# debug.net
KiCad netlist of a schematic drawn in Altium Designer
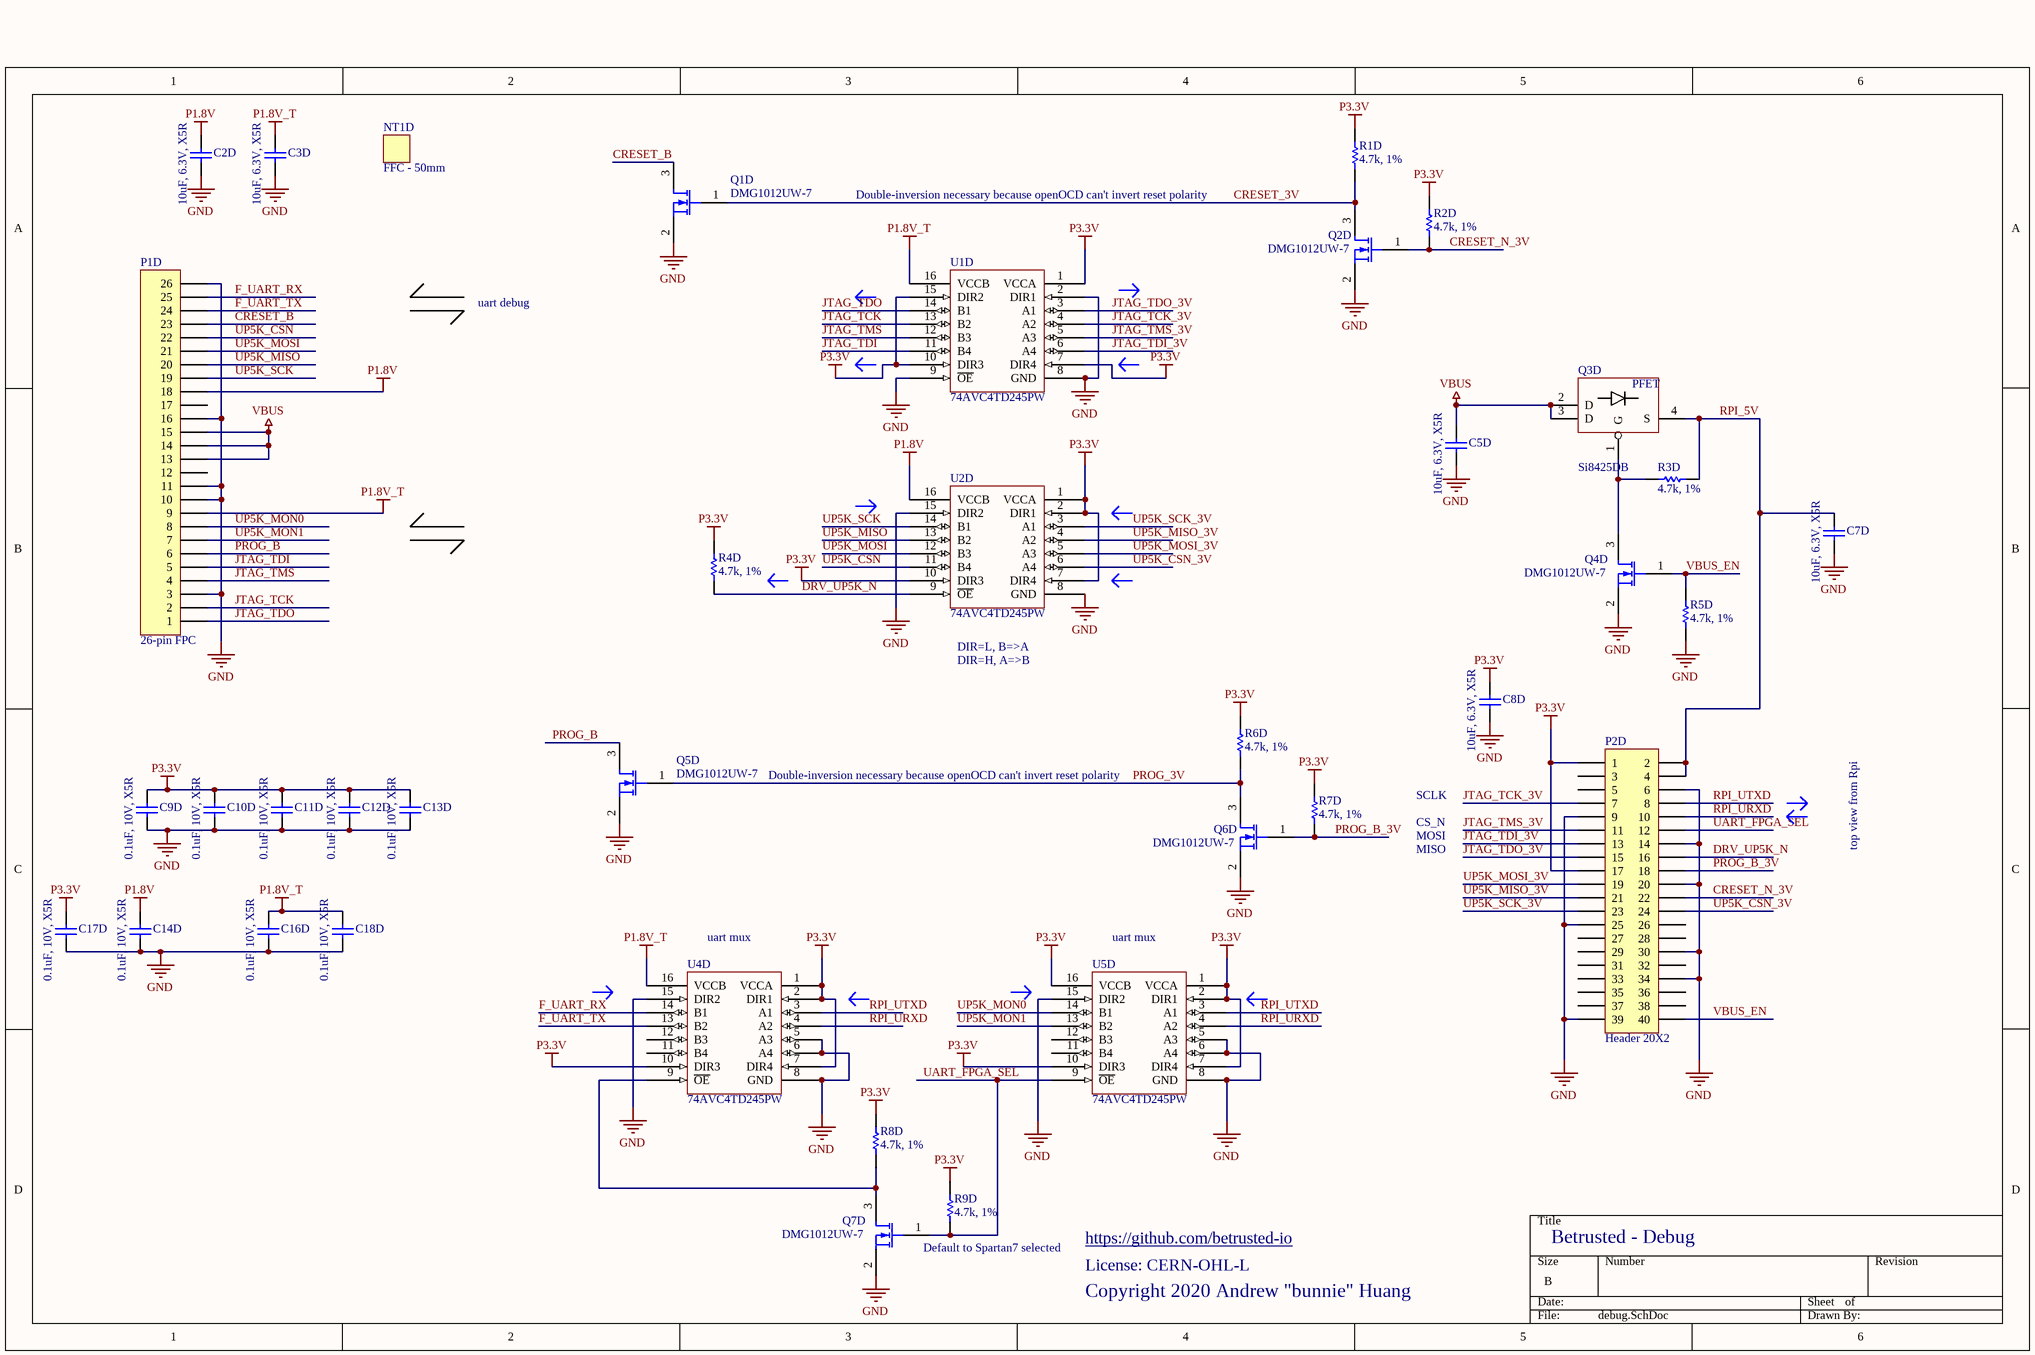
[diagram p0: debug.SchDoc]

(export (version "E")
  (design (tool "Eeschema 10.0.6"))
  (components
    (comp (ref "C2D")
      (value "10uF, 6.3V, X5R")
      (footprint "B_CAP0603")
      (description "Capacitor (Semiconductor SIM Model)")
      (fields (field (name "MPN") "CL10A106MQ8NNNC"))
      (libsource (lib "Miscellaneous Devices") (part "Cap Semi"))
    )
    (comp (ref "C3D")
      (value "10uF, 6.3V, X5R")
      (footprint "B_CAP0603")
      (description "Capacitor (Semiconductor SIM Model)")
      (fields (field (name "MPN") "CL10A106MQ8NNNC"))
      (libsource (lib "Miscellaneous Devices") (part "Cap Semi"))
    )
    (comp (ref "C5D")
      (value "10uF, 6.3V, X5R")
      (footprint "B_CAP0603")
      (description "Capacitor (Semiconductor SIM Model)")
      (fields (field (name "MPN") "CL10A106MQ8NNNC"))
      (libsource (lib "Miscellaneous Devices") (part "Cap Semi"))
    )
    (comp (ref "C7D")
      (value "10uF, 6.3V, X5R")
      (footprint "B_CAP0603")
      (description "Capacitor (Semiconductor SIM Model)")
      (fields (field (name "MPN") "CL10A106MQ8NNNC"))
      (libsource (lib "Miscellaneous Devices") (part "Cap Semi"))
    )
    (comp (ref "C8D")
      (value "10uF, 6.3V, X5R")
      (footprint "B_CAP0603")
      (description "Capacitor (Semiconductor SIM Model)")
      (fields (field (name "MPN") "CL10A106MQ8NNNC"))
      (libsource (lib "Miscellaneous Devices") (part "Cap Semi"))
    )
    (comp (ref "C9D")
      (value "0.1uF, 10V, X5R")
      (footprint "B_CAP0402")
      (description "Capacitor (Semiconductor SIM Model)")
      (fields (field (name "MPN") "CL05A104KP5NNNC"))
      (libsource (lib "Miscellaneous Devices") (part "Cap Semi"))
    )
    (comp (ref "C10D")
      (value "0.1uF, 10V, X5R")
      (footprint "B_CAP0402")
      (description "Capacitor (Semiconductor SIM Model)")
      (fields (field (name "MPN") "CL05A104KP5NNNC"))
      (libsource (lib "Miscellaneous Devices") (part "Cap Semi"))
    )
    (comp (ref "C11D")
      (value "0.1uF, 10V, X5R")
      (footprint "B_CAP0402")
      (description "Capacitor (Semiconductor SIM Model)")
      (fields (field (name "MPN") "CL05A104KP5NNNC"))
      (libsource (lib "Miscellaneous Devices") (part "Cap Semi"))
    )
    (comp (ref "C12D")
      (value "0.1uF, 10V, X5R")
      (footprint "B_CAP0402")
      (description "Capacitor (Semiconductor SIM Model)")
      (fields (field (name "MPN") "CL05A104KP5NNNC"))
      (libsource (lib "Miscellaneous Devices") (part "Cap Semi"))
    )
    (comp (ref "C13D")
      (value "0.1uF, 10V, X5R")
      (footprint "B_CAP0402")
      (description "Capacitor (Semiconductor SIM Model)")
      (fields (field (name "MPN") "CL05A104KP5NNNC"))
      (libsource (lib "Miscellaneous Devices") (part "Cap Semi"))
    )
    (comp (ref "C14D")
      (value "0.1uF, 10V, X5R")
      (footprint "B_CAP0402")
      (description "Capacitor (Semiconductor SIM Model)")
      (fields (field (name "MPN") "CL05A104KP5NNNC"))
      (libsource (lib "Miscellaneous Devices") (part "Cap Semi"))
    )
    (comp (ref "C16D")
      (value "0.1uF, 10V, X5R")
      (footprint "B_CAP0402")
      (description "Capacitor (Semiconductor SIM Model)")
      (fields (field (name "MPN") "CL05A104KP5NNNC"))
      (libsource (lib "Miscellaneous Devices") (part "Cap Semi"))
    )
    (comp (ref "C17D")
      (value "0.1uF, 10V, X5R")
      (footprint "B_CAP0402")
      (description "Capacitor (Semiconductor SIM Model)")
      (fields (field (name "MPN") "CL05A104KP5NNNC"))
      (libsource (lib "Miscellaneous Devices") (part "Cap Semi"))
    )
    (comp (ref "C18D")
      (value "0.1uF, 10V, X5R")
      (footprint "B_CAP0402")
      (description "Capacitor (Semiconductor SIM Model)")
      (fields (field (name "MPN") "CL05A104KP5NNNC"))
      (libsource (lib "Miscellaneous Devices") (part "Cap Semi"))
    )
    (comp (ref "NT1D")
      (value "FFC - 50mm")
      (description "Placeholder for non-board BOM items")
      (fields (field (name "MPN") "FJH-26-D-02.00-4"))
      (libsource (lib "commonsch") (part "NOTE"))
    )
    (comp (ref "P1D")
      (value "26-pin FPC")
      (footprint "HRS_FH34SRJ-26S-0.5SH(50)")
      (description "26 Pin FPC header")
      (fields (field (name "MPN") "FH34SRJ-26S-0.5SH(99)"))
      (libsource (lib "commonsch-new") (part "FPC-26"))
    )
    (comp (ref "P2D")
      (value "Header 20X2")
      (footprint "SAMTEC_SSW-120-01-F-D")
      (description "Header, 20-Pin, Dual row")
      (fields (field (name "MPN") "CS25402-40G-S85-C") (field (name "PUBLISHER") "Altium Limited"))
      (libsource (lib "Miscellaneous Connectors") (part "Header 20X2"))
    )
    (comp (ref "Q1D")
      (value "DMG1012UW-7")
      (footprint "SOT323-3AN")
      (description "N-Channel MOSFET")
      (fields (field (name "PUBLISHER") "Altium Limited"))
      (libsource (lib "Miscellaneous Devices") (part "MOSFET-N"))
    )
    (comp (ref "Q2D")
      (value "DMG1012UW-7")
      (footprint "SOT323-3AN")
      (description "N-Channel MOSFET")
      (fields (field (name "PUBLISHER") "Altium Limited"))
      (libsource (lib "Miscellaneous Devices") (part "MOSFET-N"))
    )
    (comp (ref "Q3D")
      (value "Si8425DB")
      (footprint "VISHAY_MICRO_FOOT_4_BUMP")
      (description "P-channel 20V 6.2A 27mOhm @ -2.5V")
      (fields (field (name "MPN") "SI8425DB-T1-E1"))
      (libsource (lib "temp-to-merge") (part "Si8425DB"))
    )
    (comp (ref "Q4D")
      (value "DMG1012UW-7")
      (footprint "SOT323-3AN")
      (description "N-Channel MOSFET")
      (fields (field (name "PUBLISHER") "Altium Limited"))
      (libsource (lib "Miscellaneous Devices") (part "MOSFET-N"))
    )
    (comp (ref "Q5D")
      (value "DMG1012UW-7")
      (footprint "SOT323-3AN")
      (description "N-Channel MOSFET")
      (fields (field (name "PUBLISHER") "Altium Limited"))
      (libsource (lib "Miscellaneous Devices") (part "MOSFET-N"))
    )
    (comp (ref "Q6D")
      (value "DMG1012UW-7")
      (footprint "SOT323-3AN")
      (description "N-Channel MOSFET")
      (fields (field (name "PUBLISHER") "Altium Limited"))
      (libsource (lib "Miscellaneous Devices") (part "MOSFET-N"))
    )
    (comp (ref "Q7D")
      (value "DMG1012UW-7")
      (footprint "SOT323-3AN")
      (description "N-Channel MOSFET")
      (fields (field (name "PUBLISHER") "Altium Limited"))
      (libsource (lib "Miscellaneous Devices") (part "MOSFET-N"))
    )
    (comp (ref "R1D")
      (value "4.7k, 1%")
      (footprint "B_RES0402")
      (description "Resistor")
      (fields (field (name "MPN") "ANY"))
      (libsource (lib "Miscellaneous Devices") (part "Res1"))
    )
    (comp (ref "R2D")
      (value "4.7k, 1%")
      (footprint "B_RES0402")
      (description "Resistor")
      (fields (field (name "MPN") "ANY"))
      (libsource (lib "Miscellaneous Devices") (part "Res1"))
    )
    (comp (ref "R3D")
      (value "4.7k, 1%")
      (footprint "B_RES0402")
      (description "Resistor")
      (fields (field (name "MPN") "ANY"))
      (libsource (lib "Miscellaneous Devices") (part "Res1"))
    )
    (comp (ref "R4D")
      (value "4.7k, 1%")
      (footprint "B_RES0402")
      (description "Resistor")
      (fields (field (name "MPN") "ANY"))
      (libsource (lib "Miscellaneous Devices") (part "Res1"))
    )
    (comp (ref "R5D")
      (value "4.7k, 1%")
      (footprint "B_RES0402")
      (description "Resistor")
      (fields (field (name "MPN") "ANY"))
      (libsource (lib "Miscellaneous Devices") (part "Res1"))
    )
    (comp (ref "R6D")
      (value "4.7k, 1%")
      (footprint "B_RES0402")
      (description "Resistor")
      (fields (field (name "MPN") "ANY"))
      (libsource (lib "Miscellaneous Devices") (part "Res1"))
    )
    (comp (ref "R7D")
      (value "4.7k, 1%")
      (footprint "B_RES0402")
      (description "Resistor")
      (fields (field (name "MPN") "ANY"))
      (libsource (lib "Miscellaneous Devices") (part "Res1"))
    )
    (comp (ref "R8D")
      (value "4.7k, 1%")
      (footprint "B_RES0402")
      (description "Resistor")
      (fields (field (name "MPN") "ANY"))
      (libsource (lib "Miscellaneous Devices") (part "Res1"))
    )
    (comp (ref "R9D")
      (value "4.7k, 1%")
      (footprint "B_RES0402")
      (description "Resistor")
      (fields (field (name "MPN") "ANY"))
      (libsource (lib "Miscellaneous Devices") (part "Res1"))
    )
    (comp (ref "U1D")
      (value "74AVC4TD245PW")
      (footprint "TSOP65P640-16AN")
      (description "4-bit dual supply translating transceiver with configurable voltage translation; 3-state")
      (libsource (lib "commonsch-new") (part "74AVC4TD245"))
    )
    (comp (ref "U2D")
      (value "74AVC4TD245PW")
      (footprint "TSOP65P640-16AN")
      (description "4-bit dual supply translating transceiver with configurable voltage translation; 3-state")
      (libsource (lib "commonsch-new") (part "74AVC4TD245"))
    )
    (comp (ref "U4D")
      (value "74AVC4TD245PW")
      (footprint "TSOP65P640-16AN")
      (description "4-bit dual supply translating transceiver with configurable voltage translation; 3-state")
      (libsource (lib "commonsch-new") (part "74AVC4TD245"))
    )
    (comp (ref "U5D")
      (value "74AVC4TD245PW")
      (footprint "TSOP65P640-16AN")
      (description "4-bit dual supply translating transceiver with configurable voltage translation; 3-state")
      (libsource (lib "commonsch-new") (part "74AVC4TD245"))
    )
  )
  (nets
    (net (code "1") (name "/CRESET_3V") (class "Default")
      (node (ref "Q1D") (pin "1") (pinfunction "G_1") (pintype "passive"))
      (node (ref "Q2D") (pin "3") (pinfunction "D_3") (pintype "passive"))
      (node (ref "R1D") (pin "1") (pinfunction "1_1") (pintype "passive"))
    )
    (net (code "2") (name "/CRESET_B") (class "Default")
      (node (ref "P1D") (pin "23") (pinfunction "23_23") (pintype "passive"))
      (node (ref "Q1D") (pin "3") (pinfunction "D_3") (pintype "passive"))
    )
    (net (code "3") (name "/CRESET_N_3V") (class "Default")
      (node (ref "P2D") (pin "22") (pinfunction "22_22") (pintype "passive"))
      (node (ref "Q2D") (pin "1") (pinfunction "G_1") (pintype "passive"))
      (node (ref "R2D") (pin "1") (pinfunction "1_1") (pintype "passive"))
    )
    (net (code "4") (name "/DRV_UP5K_N") (class "Default")
      (node (ref "P2D") (pin "16") (pinfunction "16_16") (pintype "passive"))
      (node (ref "R4D") (pin "1") (pinfunction "1_1") (pintype "passive"))
      (node (ref "U2D") (pin "9") (pinfunction "~{OE}_9") (pintype "input"))
    )
    (net (code "5") (name "/F_UART_RX") (class "Default")
      (node (ref "P1D") (pin "25") (pinfunction "25_25") (pintype "passive"))
      (node (ref "U4D") (pin "14") (pinfunction "B1_14") (pintype "bidirectional"))
    )
    (net (code "6") (name "/F_UART_TX") (class "Default")
      (node (ref "P1D") (pin "24") (pinfunction "24_24") (pintype "passive"))
      (node (ref "U4D") (pin "13") (pinfunction "B2_13") (pintype "bidirectional"))
    )
    (net (code "7") (name "/JTAG_TCK") (class "Default")
      (node (ref "P1D") (pin "2") (pinfunction "2_2") (pintype "passive"))
      (node (ref "U1D") (pin "13") (pinfunction "B2_13") (pintype "bidirectional"))
    )
    (net (code "8") (name "/JTAG_TCK_3V") (class "Default")
      (node (ref "P2D") (pin "7") (pinfunction "7_7") (pintype "passive"))
      (node (ref "U1D") (pin "4") (pinfunction "A2_4") (pintype "bidirectional"))
    )
    (net (code "9") (name "/JTAG_TDI") (class "Default")
      (node (ref "P1D") (pin "5") (pinfunction "5_5") (pintype "passive"))
      (node (ref "U1D") (pin "11") (pinfunction "B4_11") (pintype "bidirectional"))
    )
    (net (code "10") (name "/JTAG_TDI_3V") (class "Default")
      (node (ref "P2D") (pin "13") (pinfunction "13_13") (pintype "passive"))
      (node (ref "U1D") (pin "6") (pinfunction "A4_6") (pintype "bidirectional"))
    )
    (net (code "11") (name "/JTAG_TDO") (class "Default")
      (node (ref "P1D") (pin "1") (pinfunction "1_1") (pintype "passive"))
      (node (ref "U1D") (pin "14") (pinfunction "B1_14") (pintype "bidirectional"))
    )
    (net (code "12") (name "/JTAG_TDO_3V") (class "Default")
      (node (ref "P2D") (pin "15") (pinfunction "15_15") (pintype "passive"))
      (node (ref "U1D") (pin "3") (pinfunction "A1_3") (pintype "bidirectional"))
    )
    (net (code "13") (name "/JTAG_TMS") (class "Default")
      (node (ref "P1D") (pin "4") (pinfunction "4_4") (pintype "passive"))
      (node (ref "U1D") (pin "12") (pinfunction "B3_12") (pintype "bidirectional"))
    )
    (net (code "14") (name "/JTAG_TMS_3V") (class "Default")
      (node (ref "P2D") (pin "11") (pinfunction "11_11") (pintype "passive"))
      (node (ref "U1D") (pin "5") (pinfunction "A3_5") (pintype "bidirectional"))
    )
    (net (code "15") (name "/PROG_3V") (class "Default")
      (node (ref "Q5D") (pin "1") (pinfunction "G_1") (pintype "passive"))
      (node (ref "Q6D") (pin "3") (pinfunction "D_3") (pintype "passive"))
      (node (ref "R6D") (pin "1") (pinfunction "1_1") (pintype "passive"))
    )
    (net (code "16") (name "/PROG_B") (class "Default")
      (node (ref "P1D") (pin "6") (pinfunction "6_6") (pintype "passive"))
      (node (ref "Q5D") (pin "3") (pinfunction "D_3") (pintype "passive"))
    )
    (net (code "17") (name "/PROG_B_3V") (class "Default")
      (node (ref "P2D") (pin "18") (pinfunction "18_18") (pintype "passive"))
      (node (ref "Q6D") (pin "1") (pinfunction "G_1") (pintype "passive"))
      (node (ref "R7D") (pin "1") (pinfunction "1_1") (pintype "passive"))
    )
    (net (code "18") (name "/RPI_5V") (class "Default")
      (node (ref "C7D") (pin "1") (pinfunction "1_1") (pintype "passive"))
      (node (ref "P2D") (pin "2") (pinfunction "2_2") (pintype "passive"))
      (node (ref "P2D") (pin "4") (pinfunction "4_4") (pintype "passive"))
      (node (ref "Q3D") (pin "4") (pinfunction "S_4") (pintype "passive"))
      (node (ref "R3D") (pin "1") (pinfunction "1_1") (pintype "passive"))
    )
    (net (code "19") (name "/RPI_URXD") (class "Default")
      (node (ref "P2D") (pin "10") (pinfunction "10_10") (pintype "passive"))
      (node (ref "U4D") (pin "4") (pinfunction "A2_4") (pintype "bidirectional"))
      (node (ref "U5D") (pin "4") (pinfunction "A2_4") (pintype "bidirectional"))
    )
    (net (code "20") (name "/RPI_UTXD") (class "Default")
      (node (ref "P2D") (pin "8") (pinfunction "8_8") (pintype "passive"))
      (node (ref "U4D") (pin "3") (pinfunction "A1_3") (pintype "bidirectional"))
      (node (ref "U5D") (pin "3") (pinfunction "A1_3") (pintype "bidirectional"))
    )
    (net (code "21") (name "/UART_FPGA_SEL") (class "Default")
      (node (ref "P2D") (pin "12") (pinfunction "12_12") (pintype "passive"))
      (node (ref "Q7D") (pin "1") (pinfunction "G_1") (pintype "passive"))
      (node (ref "R9D") (pin "1") (pinfunction "1_1") (pintype "passive"))
      (node (ref "U5D") (pin "9") (pinfunction "~{OE}_9") (pintype "input"))
    )
    (net (code "22") (name "/UP5K_CSN") (class "Default")
      (node (ref "P1D") (pin "22") (pinfunction "22_22") (pintype "passive"))
      (node (ref "U2D") (pin "11") (pinfunction "B4_11") (pintype "bidirectional"))
    )
    (net (code "23") (name "/UP5K_CSN_3V") (class "Default")
      (node (ref "P2D") (pin "24") (pinfunction "24_24") (pintype "passive"))
      (node (ref "U2D") (pin "6") (pinfunction "A4_6") (pintype "bidirectional"))
    )
    (net (code "24") (name "/UP5K_MISO") (class "Default")
      (node (ref "P1D") (pin "20") (pinfunction "20_20") (pintype "passive"))
      (node (ref "U2D") (pin "13") (pinfunction "B2_13") (pintype "bidirectional"))
    )
    (net (code "25") (name "/UP5K_MISO_3V") (class "Default")
      (node (ref "P2D") (pin "21") (pinfunction "21_21") (pintype "passive"))
      (node (ref "U2D") (pin "4") (pinfunction "A2_4") (pintype "bidirectional"))
    )
    (net (code "26") (name "/UP5K_MON0") (class "Default")
      (node (ref "P1D") (pin "8") (pinfunction "8_8") (pintype "passive"))
      (node (ref "U5D") (pin "14") (pinfunction "B1_14") (pintype "bidirectional"))
    )
    (net (code "27") (name "/UP5K_MON1") (class "Default")
      (node (ref "P1D") (pin "7") (pinfunction "7_7") (pintype "passive"))
      (node (ref "U5D") (pin "13") (pinfunction "B2_13") (pintype "bidirectional"))
    )
    (net (code "28") (name "/UP5K_MOSI") (class "Default")
      (node (ref "P1D") (pin "21") (pinfunction "21_21") (pintype "passive"))
      (node (ref "U2D") (pin "12") (pinfunction "B3_12") (pintype "bidirectional"))
    )
    (net (code "29") (name "/UP5K_MOSI_3V") (class "Default")
      (node (ref "P2D") (pin "19") (pinfunction "19_19") (pintype "passive"))
      (node (ref "U2D") (pin "5") (pinfunction "A3_5") (pintype "bidirectional"))
    )
    (net (code "30") (name "/UP5K_SCK") (class "Default")
      (node (ref "P1D") (pin "19") (pinfunction "19_19") (pintype "passive"))
      (node (ref "U2D") (pin "14") (pinfunction "B1_14") (pintype "bidirectional"))
    )
    (net (code "31") (name "/UP5K_SCK_3V") (class "Default")
      (node (ref "P2D") (pin "23") (pinfunction "23_23") (pintype "passive"))
      (node (ref "U2D") (pin "3") (pinfunction "A1_3") (pintype "bidirectional"))
    )
    (net (code "32") (name "/VBUS_EN") (class "Default")
      (node (ref "P2D") (pin "40") (pinfunction "40_40") (pintype "passive"))
      (node (ref "Q4D") (pin "1") (pinfunction "G_1") (pintype "passive"))
      (node (ref "R5D") (pin "2") (pinfunction "2_2") (pintype "passive"))
    )
    (net (code "33") (name "GND") (class "Default")
      (node (ref "C10D") (pin "2") (pinfunction "2_2") (pintype "passive"))
      (node (ref "C11D") (pin "2") (pinfunction "2_2") (pintype "passive"))
      (node (ref "C12D") (pin "2") (pinfunction "2_2") (pintype "passive"))
      (node (ref "C13D") (pin "2") (pinfunction "2_2") (pintype "passive"))
      (node (ref "C14D") (pin "2") (pinfunction "2_2") (pintype "passive"))
      (node (ref "C16D") (pin "2") (pinfunction "2_2") (pintype "passive"))
      (node (ref "C17D") (pin "2") (pinfunction "2_2") (pintype "passive"))
      (node (ref "C18D") (pin "2") (pinfunction "2_2") (pintype "passive"))
      (node (ref "C2D") (pin "2") (pinfunction "2_2") (pintype "passive"))
      (node (ref "C3D") (pin "2") (pinfunction "2_2") (pintype "passive"))
      (node (ref "C5D") (pin "2") (pinfunction "2_2") (pintype "passive"))
      (node (ref "C7D") (pin "2") (pinfunction "2_2") (pintype "passive"))
      (node (ref "C8D") (pin "2") (pinfunction "2_2") (pintype "passive"))
      (node (ref "C9D") (pin "2") (pinfunction "2_2") (pintype "passive"))
      (node (ref "P1D") (pin "10") (pinfunction "10_10") (pintype "passive"))
      (node (ref "P1D") (pin "11") (pinfunction "11_11") (pintype "passive"))
      (node (ref "P1D") (pin "16") (pinfunction "16_16") (pintype "passive"))
      (node (ref "P1D") (pin "26") (pinfunction "26_26") (pintype "passive"))
      (node (ref "P1D") (pin "3") (pinfunction "3_3") (pintype "passive"))
      (node (ref "P2D") (pin "14") (pinfunction "14_14") (pintype "passive"))
      (node (ref "P2D") (pin "20") (pinfunction "20_20") (pintype "passive"))
      (node (ref "P2D") (pin "25") (pinfunction "25_25") (pintype "passive"))
      (node (ref "P2D") (pin "30") (pinfunction "30_30") (pintype "passive"))
      (node (ref "P2D") (pin "34") (pinfunction "34_34") (pintype "passive"))
      (node (ref "P2D") (pin "39") (pinfunction "39_39") (pintype "passive"))
      (node (ref "P2D") (pin "6") (pinfunction "6_6") (pintype "passive"))
      (node (ref "P2D") (pin "9") (pinfunction "9_9") (pintype "passive"))
      (node (ref "Q1D") (pin "2") (pinfunction "S_2") (pintype "passive"))
      (node (ref "Q2D") (pin "2") (pinfunction "S_2") (pintype "passive"))
      (node (ref "Q4D") (pin "2") (pinfunction "S_2") (pintype "passive"))
      (node (ref "Q5D") (pin "2") (pinfunction "S_2") (pintype "passive"))
      (node (ref "Q6D") (pin "2") (pinfunction "S_2") (pintype "passive"))
      (node (ref "Q7D") (pin "2") (pinfunction "S_2") (pintype "passive"))
      (node (ref "R5D") (pin "1") (pinfunction "1_1") (pintype "passive"))
      (node (ref "U1D") (pin "2") (pinfunction "DIR1_2") (pintype "input"))
      (node (ref "U1D") (pin "8") (pinfunction "GND_8") (pintype "power_in"))
      (node (ref "U1D") (pin "9") (pinfunction "~{OE}_9") (pintype "input"))
      (node (ref "U2D") (pin "15") (pinfunction "DIR2_15") (pintype "input"))
      (node (ref "U2D") (pin "8") (pinfunction "GND_8") (pintype "power_in"))
      (node (ref "U4D") (pin "15") (pinfunction "DIR2_15") (pintype "input"))
      (node (ref "U4D") (pin "5") (pinfunction "A3_5") (pintype "bidirectional"))
      (node (ref "U4D") (pin "6") (pinfunction "A4_6") (pintype "bidirectional"))
      (node (ref "U4D") (pin "8") (pinfunction "GND_8") (pintype "power_in"))
      (node (ref "U5D") (pin "15") (pinfunction "DIR2_15") (pintype "input"))
      (node (ref "U5D") (pin "5") (pinfunction "A3_5") (pintype "bidirectional"))
      (node (ref "U5D") (pin "6") (pinfunction "A4_6") (pintype "bidirectional"))
      (node (ref "U5D") (pin "8") (pinfunction "GND_8") (pintype "power_in"))
    )
    (net (code "34") (name "Net-(Q3D-G)") (class "Default")
      (node (ref "Q3D") (pin "1") (pinfunction "G_1") (pintype "passive"))
      (node (ref "Q4D") (pin "3") (pinfunction "D_3") (pintype "passive"))
      (node (ref "R3D") (pin "2") (pinfunction "2_2") (pintype "passive"))
    )
    (net (code "35") (name "Net-(Q7D-D)") (class "Default")
      (node (ref "Q7D") (pin "3") (pinfunction "D_3") (pintype "passive"))
      (node (ref "R8D") (pin "1") (pinfunction "1_1") (pintype "passive"))
      (node (ref "U4D") (pin "9") (pinfunction "~{OE}_9") (pintype "input"))
    )
    (net (code "36") (name "P1.8V") (class "Default")
      (node (ref "C14D") (pin "1") (pinfunction "1_1") (pintype "passive"))
      (node (ref "C2D") (pin "1") (pinfunction "1_1") (pintype "passive"))
      (node (ref "P1D") (pin "18") (pinfunction "18_18") (pintype "passive"))
      (node (ref "U2D") (pin "16") (pinfunction "VCCB_16") (pintype "power_in"))
    )
    (net (code "37") (name "P1.8V_T") (class "Default")
      (node (ref "C16D") (pin "1") (pinfunction "1_1") (pintype "passive"))
      (node (ref "C18D") (pin "1") (pinfunction "1_1") (pintype "passive"))
      (node (ref "C3D") (pin "1") (pinfunction "1_1") (pintype "passive"))
      (node (ref "P1D") (pin "9") (pinfunction "9_9") (pintype "passive"))
      (node (ref "U1D") (pin "16") (pinfunction "VCCB_16") (pintype "power_in"))
      (node (ref "U4D") (pin "16") (pinfunction "VCCB_16") (pintype "power_in"))
    )
    (net (code "38") (name "P3.3V") (class "Default")
      (node (ref "C10D") (pin "1") (pinfunction "1_1") (pintype "passive"))
      (node (ref "C11D") (pin "1") (pinfunction "1_1") (pintype "passive"))
      (node (ref "C12D") (pin "1") (pinfunction "1_1") (pintype "passive"))
      (node (ref "C13D") (pin "1") (pinfunction "1_1") (pintype "passive"))
      (node (ref "C17D") (pin "1") (pinfunction "1_1") (pintype "passive"))
      (node (ref "C8D") (pin "1") (pinfunction "1_1") (pintype "passive"))
      (node (ref "C9D") (pin "1") (pinfunction "1_1") (pintype "passive"))
      (node (ref "P2D") (pin "1") (pinfunction "1_1") (pintype "passive"))
      (node (ref "P2D") (pin "17") (pinfunction "17_17") (pintype "passive"))
      (node (ref "R1D") (pin "2") (pinfunction "2_2") (pintype "passive"))
      (node (ref "R2D") (pin "2") (pinfunction "2_2") (pintype "passive"))
      (node (ref "R4D") (pin "2") (pinfunction "2_2") (pintype "passive"))
      (node (ref "R6D") (pin "2") (pinfunction "2_2") (pintype "passive"))
      (node (ref "R7D") (pin "2") (pinfunction "2_2") (pintype "passive"))
      (node (ref "R8D") (pin "2") (pinfunction "2_2") (pintype "passive"))
      (node (ref "R9D") (pin "2") (pinfunction "2_2") (pintype "passive"))
      (node (ref "U1D") (pin "1") (pinfunction "VCCA_1") (pintype "power_in"))
      (node (ref "U1D") (pin "10") (pinfunction "DIR3_10") (pintype "input"))
      (node (ref "U1D") (pin "15") (pinfunction "DIR2_15") (pintype "input"))
      (node (ref "U1D") (pin "7") (pinfunction "DIR4_7") (pintype "input"))
      (node (ref "U2D") (pin "1") (pinfunction "VCCA_1") (pintype "power_in"))
      (node (ref "U2D") (pin "10") (pinfunction "DIR3_10") (pintype "input"))
      (node (ref "U2D") (pin "2") (pinfunction "DIR1_2") (pintype "input"))
      (node (ref "U2D") (pin "7") (pinfunction "DIR4_7") (pintype "input"))
      (node (ref "U4D") (pin "1") (pinfunction "VCCA_1") (pintype "power_in"))
      (node (ref "U4D") (pin "10") (pinfunction "DIR3_10") (pintype "input"))
      (node (ref "U4D") (pin "2") (pinfunction "DIR1_2") (pintype "input"))
      (node (ref "U4D") (pin "7") (pinfunction "DIR4_7") (pintype "input"))
      (node (ref "U5D") (pin "1") (pinfunction "VCCA_1") (pintype "power_in"))
      (node (ref "U5D") (pin "10") (pinfunction "DIR3_10") (pintype "input"))
      (node (ref "U5D") (pin "16") (pinfunction "VCCB_16") (pintype "power_in"))
      (node (ref "U5D") (pin "2") (pinfunction "DIR1_2") (pintype "input"))
      (node (ref "U5D") (pin "7") (pinfunction "DIR4_7") (pintype "input"))
    )
    (net (code "39") (name "VBUS") (class "Default")
      (node (ref "C5D") (pin "1") (pinfunction "1_1") (pintype "passive"))
      (node (ref "P1D") (pin "13") (pinfunction "13_13") (pintype "passive"))
      (node (ref "P1D") (pin "14") (pinfunction "14_14") (pintype "passive"))
      (node (ref "P1D") (pin "15") (pinfunction "15_15") (pintype "passive"))
      (node (ref "Q3D") (pin "2") (pinfunction "D_2") (pintype "passive"))
      (node (ref "Q3D") (pin "3") (pinfunction "D_3") (pintype "passive"))
    )
    (net (code "40") (name "unconnected-(P1D-Pad12)") (class "Default")
      (node (ref "P1D") (pin "12") (pinfunction "12_12") (pintype "passive"))
    )
    (net (code "41") (name "unconnected-(P1D-Pad17)") (class "Default")
      (node (ref "P1D") (pin "17") (pinfunction "17_17") (pintype "passive"))
    )
    (net (code "42") (name "unconnected-(P2D-Pad3)") (class "Default")
      (node (ref "P2D") (pin "3") (pinfunction "3_3") (pintype "passive"))
    )
    (net (code "43") (name "unconnected-(P2D-Pad5)") (class "Default")
      (node (ref "P2D") (pin "5") (pinfunction "5_5") (pintype "passive"))
    )
    (net (code "44") (name "unconnected-(P2D-Pad26)") (class "Default")
      (node (ref "P2D") (pin "26") (pinfunction "26_26") (pintype "passive"))
    )
    (net (code "45") (name "unconnected-(P2D-Pad27)") (class "Default")
      (node (ref "P2D") (pin "27") (pinfunction "27_27") (pintype "passive"))
    )
    (net (code "46") (name "unconnected-(P2D-Pad28)") (class "Default")
      (node (ref "P2D") (pin "28") (pinfunction "28_28") (pintype "passive"))
    )
    (net (code "47") (name "unconnected-(P2D-Pad29)") (class "Default")
      (node (ref "P2D") (pin "29") (pinfunction "29_29") (pintype "passive"))
    )
    (net (code "48") (name "unconnected-(P2D-Pad31)") (class "Default")
      (node (ref "P2D") (pin "31") (pinfunction "31_31") (pintype "passive"))
    )
    (net (code "49") (name "unconnected-(P2D-Pad32)") (class "Default")
      (node (ref "P2D") (pin "32") (pinfunction "32_32") (pintype "passive"))
    )
    (net (code "50") (name "unconnected-(P2D-Pad33)") (class "Default")
      (node (ref "P2D") (pin "33") (pinfunction "33_33") (pintype "passive"))
    )
    (net (code "51") (name "unconnected-(P2D-Pad35)") (class "Default")
      (node (ref "P2D") (pin "35") (pinfunction "35_35") (pintype "passive"))
    )
    (net (code "52") (name "unconnected-(P2D-Pad36)") (class "Default")
      (node (ref "P2D") (pin "36") (pinfunction "36_36") (pintype "passive"))
    )
    (net (code "53") (name "unconnected-(P2D-Pad37)") (class "Default")
      (node (ref "P2D") (pin "37") (pinfunction "37_37") (pintype "passive"))
    )
    (net (code "54") (name "unconnected-(P2D-Pad38)") (class "Default")
      (node (ref "P2D") (pin "38") (pinfunction "38_38") (pintype "passive"))
    )
    (net (code "55") (name "unconnected-(U4D-B3-Pad12)") (class "Default")
      (node (ref "U4D") (pin "12") (pinfunction "B3_12") (pintype "bidirectional"))
    )
    (net (code "56") (name "unconnected-(U4D-B4-Pad11)") (class "Default")
      (node (ref "U4D") (pin "11") (pinfunction "B4_11") (pintype "bidirectional"))
    )
    (net (code "57") (name "unconnected-(U5D-B3-Pad12)") (class "Default")
      (node (ref "U5D") (pin "12") (pinfunction "B3_12") (pintype "bidirectional"))
    )
    (net (code "58") (name "unconnected-(U5D-B4-Pad11)") (class "Default")
      (node (ref "U5D") (pin "11") (pinfunction "B4_11") (pintype "bidirectional"))
    )
  )
)
